# attiny1l.net
KiCad netlist of a schematic drawn in EAGLE
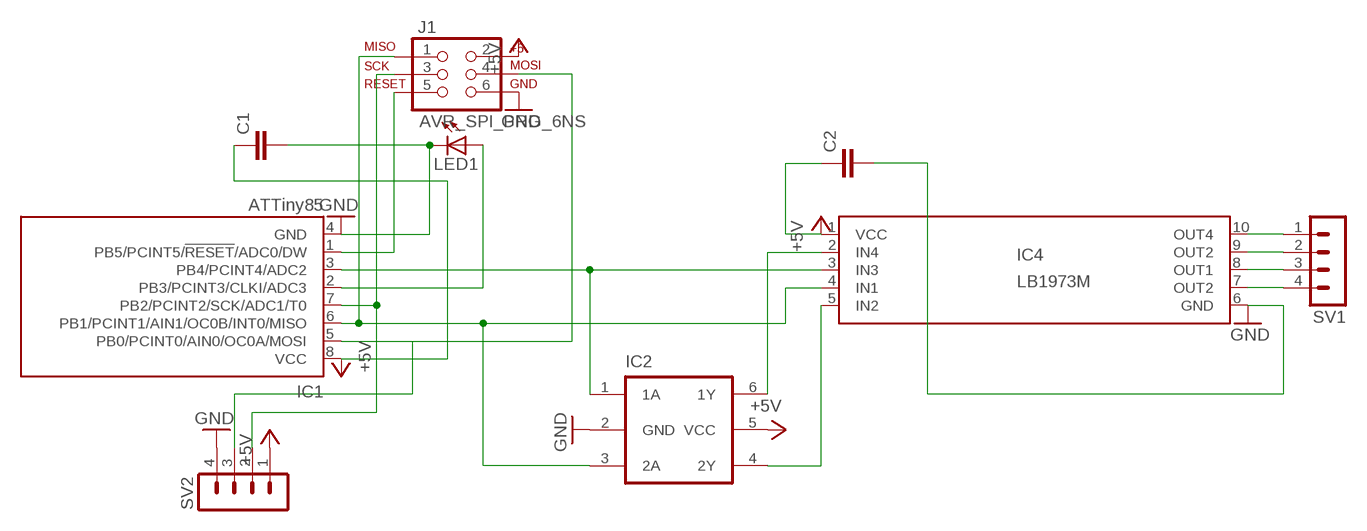
[diagram p0: schematic, sheet 1]

(export (version "E")
  (design (tool "Eeschema 10.0.6"))
  (components
    (comp (ref "C1")
      (value "C-EUC0805")
      (footprint "eagle-import:C0805")
      (libsource (lib "eagle-import") (part "C-EUC0805"))
    )
    (comp (ref "C2")
      (value "C-EUC0805")
      (footprint "eagle-import:C0805")
      (libsource (lib "eagle-import") (part "C-EUC0805"))
    )
    (comp (ref "IC1")
      (value "ATTiny85")
      (footprint "eagle-import:8S2")
      (fields (field (name "MPN") "ATTINY13-20SU"))
      (libsource (lib "eagle-import") (part "TINY13SU-20"))
    )
    (comp (ref "IC2")
      (value "IC_BUFF_SN74LVC2G17DBV")
      (footprint "eagle-import:DBV-R-PDSO-G6")
      (libsource (lib "eagle-import") (part "IC_BUFF_SN74LVC2G17DBV"))
    )
    (comp (ref "IC4")
      (value "LB1973M")
      (footprint "eagle-import:SSOP10")
      (libsource (lib "eagle-import") (part "LB1973M"))
    )
    (comp (ref "J1")
      (value "AVR_SPI_PRG_6NS")
      (footprint "eagle-import:2X3-NS")
      (libsource (lib "eagle-import") (part "AVR_SPI_PRG_6NS"))
    )
    (comp (ref "LED1")
      (value "LED0603")
      (footprint "eagle-import:LED-0603")
      (libsource (lib "eagle-import") (part "LED0603"))
    )
    (comp (ref "SV1")
      (value "MA04-1")
      (footprint "eagle-import:MA04-1")
      (libsource (lib "eagle-import") (part "MA04-1"))
    )
    (comp (ref "SV2")
      (value "MA04-1")
      (footprint "eagle-import:MA04-1")
      (libsource (lib "eagle-import") (part "MA04-1"))
    )
  )
  (nets
    (net (code "1") (name "+5V") (class "Default")
      (node (ref "C1") (pin "1") (pinfunction "1_1") (pintype "passive"))
      (node (ref "C2") (pin "1") (pinfunction "1_1") (pintype "passive"))
      (node (ref "IC1") (pin "8") (pinfunction "VCC_8") (pintype "power_in"))
      (node (ref "IC2") (pin "5") (pinfunction "VCC_5") (pintype "bidirectional"))
      (node (ref "IC4") (pin "1") (pinfunction "VCC_1") (pintype "power_in"))
      (node (ref "J1") (pin "2") (pinfunction "2_2") (pintype "passive"))
      (node (ref "SV2") (pin "1") (pinfunction "1_1") (pintype "passive"))
    )
    (net (code "2") (name "GND") (class "Default")
      (node (ref "C1") (pin "2") (pinfunction "2_2") (pintype "passive"))
      (node (ref "C2") (pin "2") (pinfunction "2_2") (pintype "passive"))
      (node (ref "IC1") (pin "4") (pinfunction "GND_4") (pintype "power_in"))
      (node (ref "IC2") (pin "2") (pinfunction "GND_2") (pintype "bidirectional"))
      (node (ref "IC4") (pin "6") (pinfunction "GND_6") (pintype "power_in"))
      (node (ref "J1") (pin "6") (pinfunction "6_6") (pintype "passive"))
      (node (ref "LED1") (pin "C") (pinfunction "C_C") (pintype "passive"))
      (node (ref "SV2") (pin "4") (pinfunction "4_4") (pintype "passive"))
    )
    (net (code "3") (name "Net-(IC1-PB0{slash}PCINT0{slash}AIN0{slash}OC0A{slash}MOSI)") (class "Default")
      (node (ref "IC1") (pin "5") (pinfunction "PB0/PCINT0/AIN0/OC0A/MOSI_5") (pintype "bidirectional"))
      (node (ref "J1") (pin "4") (pinfunction "4_4") (pintype "passive"))
      (node (ref "SV2") (pin "3") (pinfunction "3_3") (pintype "passive"))
    )
    (net (code "4") (name "Net-(IC1-PB1{slash}PCINT1{slash}AIN1{slash}OC0B{slash}INT0{slash}MISO)") (class "Default")
      (node (ref "IC1") (pin "6") (pinfunction "PB1/PCINT1/AIN1/OC0B/INT0/MISO_6") (pintype "bidirectional"))
      (node (ref "IC2") (pin "3") (pinfunction "2A_3") (pintype "bidirectional"))
      (node (ref "IC4") (pin "4") (pinfunction "IN1_4") (pintype "input"))
      (node (ref "J1") (pin "1") (pinfunction "1_1") (pintype "passive"))
    )
    (net (code "5") (name "Net-(IC1-PB2{slash}PCINT2{slash}SCK{slash}ADC1{slash}T0)") (class "Default")
      (node (ref "IC1") (pin "7") (pinfunction "PB2/PCINT2/SCK/ADC1/T0_7") (pintype "bidirectional"))
      (node (ref "J1") (pin "3") (pinfunction "3_3") (pintype "passive"))
      (node (ref "SV2") (pin "2") (pinfunction "2_2") (pintype "passive"))
    )
    (net (code "6") (name "Net-(IC1-PB3{slash}PCINT3{slash}CLKI{slash}ADC3)") (class "Default")
      (node (ref "IC1") (pin "2") (pinfunction "PB3/PCINT3/CLKI/ADC3_2") (pintype "bidirectional"))
      (node (ref "LED1") (pin "A") (pinfunction "A_A") (pintype "passive"))
    )
    (net (code "7") (name "Net-(IC1-PB4{slash}PCINT4{slash}ADC2)") (class "Default")
      (node (ref "IC1") (pin "3") (pinfunction "PB4/PCINT4/ADC2_3") (pintype "bidirectional"))
      (node (ref "IC2") (pin "1") (pinfunction "1A_1") (pintype "bidirectional"))
      (node (ref "IC4") (pin "3") (pinfunction "IN3_3") (pintype "input"))
    )
    (net (code "8") (name "Net-(IC1-PB5{slash}PCINT5{slash}~{RESET}{slash}ADC0{slash}DW)") (class "Default")
      (node (ref "IC1") (pin "1") (pinfunction "PB5/PCINT5/~{RESET}/ADC0/DW_1") (pintype "bidirectional"))
      (node (ref "J1") (pin "5") (pinfunction "5_5") (pintype "passive"))
    )
    (net (code "9") (name "Net-(IC2-1Y)") (class "Default")
      (node (ref "IC2") (pin "6") (pinfunction "1Y_6") (pintype "bidirectional"))
      (node (ref "IC4") (pin "2") (pinfunction "IN4_2") (pintype "input"))
    )
    (net (code "10") (name "Net-(IC2-2Y)") (class "Default")
      (node (ref "IC2") (pin "4") (pinfunction "2Y_4") (pintype "bidirectional"))
      (node (ref "IC4") (pin "5") (pinfunction "IN2_5") (pintype "input"))
    )
    (net (code "11") (name "Net-(IC4-OUT1)") (class "Default")
      (node (ref "IC4") (pin "8") (pinfunction "OUT1_8") (pintype "output"))
      (node (ref "SV1") (pin "3") (pinfunction "3_3") (pintype "passive"))
    )
    (net (code "12") (name "Net-(IC4-OUT2-Pad7)") (class "Default")
      (node (ref "IC4") (pin "7") (pinfunction "OUT2_7") (pintype "output"))
      (node (ref "SV1") (pin "4") (pinfunction "4_4") (pintype "passive"))
    )
    (net (code "13") (name "Net-(IC4-OUT2-Pad9)") (class "Default")
      (node (ref "IC4") (pin "9") (pinfunction "OUT2_9") (pintype "output"))
      (node (ref "SV1") (pin "2") (pinfunction "2_2") (pintype "passive"))
    )
    (net (code "14") (name "Net-(IC4-OUT4)") (class "Default")
      (node (ref "IC4") (pin "10") (pinfunction "OUT4_10") (pintype "output"))
      (node (ref "SV1") (pin "1") (pinfunction "1_1") (pintype "passive"))
    )
  )
)
